# CoderDojo_Controller.net
KiCad netlist of a schematic drawn in EAGLE
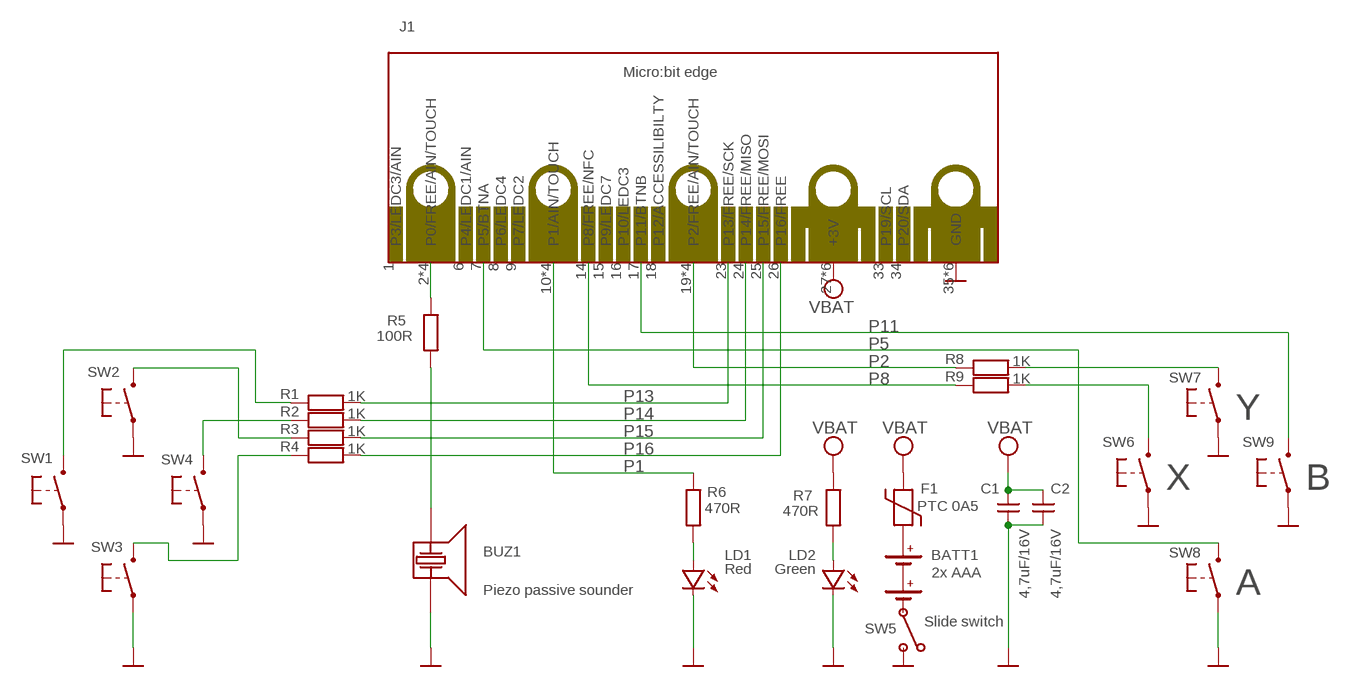
[diagram p0: schematic, sheet 1]

(export (version "E")
  (design (tool "Eeschema 10.0.6"))
  (components
    (comp (ref "BATT1")
      (value "CJ2XAAA")
      (footprint "eagle-import:SOCKET_2XAAA")
      (fields (field (name "VALUE_SHOWN") "2x AAA"))
      (libsource (lib "eagle-import") (part "CJ2XAAA"))
    )
    (comp (ref "BUZ1")
      (value "CBUZ9")
      (footprint "eagle-import:BUZZER9")
      (libsource (lib "eagle-import") (part "CBUZ9"))
    )
    (comp (ref "C1")
      (value "CC4U7A")
      (footprint "eagle-import:CAP_1206")
      (fields (field (name "VALUE_SHOWN") "4,7uF/16V"))
      (libsource (lib "eagle-import") (part "CC4U7A"))
    )
    (comp (ref "C2")
      (value "CC4U7A")
      (footprint "eagle-import:CAP_1206")
      (fields (field (name "VALUE_SHOWN") "4,7uF/16V"))
      (libsource (lib "eagle-import") (part "CC4U7A"))
    )
    (comp (ref "F1")
      (value "CFPOLY0A5B")
      (footprint "eagle-import:RES_1812")
      (fields (field (name "VALUE_SHOWN") "PTC 0A5"))
      (libsource (lib "eagle-import") (part "CFPOLY0A5B"))
    )
    (comp (ref "J1")
      (value "CJMBITH")
      (footprint "eagle-import:SOCKET_MBIT_H")
      (fields (field (name "VALUE_SHOWN") "Micro:bit edge"))
      (libsource (lib "eagle-import") (part "CJMBITH"))
    )
    (comp (ref "LD1")
      (value "CDLEDRDC")
      (footprint "eagle-import:LED_0805")
      (fields (field (name "VALUE_SHOWN") "Red"))
      (libsource (lib "eagle-import") (part "CDLEDRDC"))
    )
    (comp (ref "LD2")
      (value "CDLEDGNC")
      (footprint "eagle-import:LED_0805")
      (fields (field (name "VALUE_SHOWN") "Green"))
      (libsource (lib "eagle-import") (part "CDLEDGNC"))
    )
    (comp (ref "R1")
      (value "CR1KA")
      (footprint "eagle-import:RES_0805")
      (fields (field (name "VALUE_SHOWN") "1K"))
      (libsource (lib "eagle-import") (part "CR1KA"))
    )
    (comp (ref "R2")
      (value "CR1KA")
      (footprint "eagle-import:RES_0805")
      (fields (field (name "VALUE_SHOWN") "1K"))
      (libsource (lib "eagle-import") (part "CR1KA"))
    )
    (comp (ref "R3")
      (value "CR1KA")
      (footprint "eagle-import:RES_0805")
      (fields (field (name "VALUE_SHOWN") "1K"))
      (libsource (lib "eagle-import") (part "CR1KA"))
    )
    (comp (ref "R4")
      (value "CR1KA")
      (footprint "eagle-import:RES_0805")
      (fields (field (name "VALUE_SHOWN") "1K"))
      (libsource (lib "eagle-import") (part "CR1KA"))
    )
    (comp (ref "R5")
      (value "CR100RA")
      (footprint "eagle-import:RES_0805")
      (fields (field (name "VALUE_SHOWN") "100R"))
      (libsource (lib "eagle-import") (part "CR100RA"))
    )
    (comp (ref "R6")
      (value "CR470RA")
      (footprint "eagle-import:RES_0805")
      (fields (field (name "VALUE_SHOWN") "470R"))
      (libsource (lib "eagle-import") (part "CR470RA"))
    )
    (comp (ref "R7")
      (value "CR470RA")
      (footprint "eagle-import:RES_0805")
      (fields (field (name "VALUE_SHOWN") "470R"))
      (libsource (lib "eagle-import") (part "CR470RA"))
    )
    (comp (ref "R8")
      (value "CR1KA")
      (footprint "eagle-import:RES_0805")
      (fields (field (name "VALUE_SHOWN") "1K"))
      (libsource (lib "eagle-import") (part "CR1KA"))
    )
    (comp (ref "R9")
      (value "CR1KA")
      (footprint "eagle-import:RES_0805")
      (fields (field (name "VALUE_SHOWN") "1K"))
      (libsource (lib "eagle-import") (part "CR1KA"))
    )
    (comp (ref "SW1")
      (value "CSWPUSHA5")
      (footprint "eagle-import:SWITCH_PUSH_5MM")
      (libsource (lib "eagle-import") (part "CSWPUSHA5"))
    )
    (comp (ref "SW2")
      (value "CSWPUSHA5")
      (footprint "eagle-import:SWITCH_PUSH_5MM")
      (libsource (lib "eagle-import") (part "CSWPUSHA5"))
    )
    (comp (ref "SW3")
      (value "CSWPUSHA5")
      (footprint "eagle-import:SWITCH_PUSH_5MM")
      (libsource (lib "eagle-import") (part "CSWPUSHA5"))
    )
    (comp (ref "SW4")
      (value "CSWPUSHA5")
      (footprint "eagle-import:SWITCH_PUSH_5MM")
      (libsource (lib "eagle-import") (part "CSWPUSHA5"))
    )
    (comp (ref "SW5")
      (value "CSWSS12F23")
      (footprint "eagle-import:SWITCH_SS12F23")
      (fields (field (name "VALUE_SHOWN") "Slide switch"))
      (libsource (lib "eagle-import") (part "CSWSS12F23"))
    )
    (comp (ref "SW6")
      (value "CSWPUSHA5")
      (footprint "eagle-import:SWITCH_PUSH_5MM")
      (libsource (lib "eagle-import") (part "CSWPUSHA5"))
    )
    (comp (ref "SW7")
      (value "CSWPUSHA5")
      (footprint "eagle-import:SWITCH_PUSH_5MM")
      (libsource (lib "eagle-import") (part "CSWPUSHA5"))
    )
    (comp (ref "SW8")
      (value "CSWPUSHA5")
      (footprint "eagle-import:SWITCH_PUSH_5MM")
      (libsource (lib "eagle-import") (part "CSWPUSHA5"))
    )
    (comp (ref "SW9")
      (value "CSWPUSHA5")
      (footprint "eagle-import:SWITCH_PUSH_5MM")
      (libsource (lib "eagle-import") (part "CSWPUSHA5"))
    )
  )
  (nets
    (net (code "1") (name "/P1") (class "Default")
      (node (ref "J1") (pin "10") (pinfunction "P1/AIN/TOUCH_10") (pintype "bidirectional"))
      (node (ref "J1") (pin "11") (pinfunction "P1/AIN/TOUCH_11") (pintype "bidirectional"))
      (node (ref "J1") (pin "12") (pinfunction "P1/AIN/TOUCH_12") (pintype "bidirectional"))
      (node (ref "J1") (pin "13") (pinfunction "P1/AIN/TOUCH_13") (pintype "bidirectional"))
      (node (ref "R6") (pin "2") (pinfunction "2_2") (pintype "passive"))
    )
    (net (code "2") (name "/P2") (class "Default")
      (node (ref "J1") (pin "19") (pinfunction "P2/FREE/AIN/TOUCH_19") (pintype "bidirectional"))
      (node (ref "J1") (pin "20") (pinfunction "P2/FREE/AIN/TOUCH_20") (pintype "bidirectional"))
      (node (ref "J1") (pin "21") (pinfunction "P2/FREE/AIN/TOUCH_21") (pintype "bidirectional"))
      (node (ref "J1") (pin "22") (pinfunction "P2/FREE/AIN/TOUCH_22") (pintype "bidirectional"))
      (node (ref "R8") (pin "1") (pinfunction "1_1") (pintype "passive"))
    )
    (net (code "3") (name "/P5") (class "Default")
      (node (ref "J1") (pin "7") (pinfunction "P5/BTNA_7") (pintype "bidirectional"))
      (node (ref "SW8") (pin "1") (pinfunction "S_1") (pintype "passive"))
      (node (ref "SW8") (pin "2") (pinfunction "S_2") (pintype "passive"))
    )
    (net (code "4") (name "/P8") (class "Default")
      (node (ref "J1") (pin "14") (pinfunction "P8/FREE/NFC_14") (pintype "bidirectional"))
      (node (ref "R9") (pin "1") (pinfunction "1_1") (pintype "passive"))
    )
    (net (code "5") (name "/P11") (class "Default")
      (node (ref "J1") (pin "17") (pinfunction "P11/BTNB_17") (pintype "bidirectional"))
      (node (ref "SW9") (pin "1") (pinfunction "S_1") (pintype "passive"))
      (node (ref "SW9") (pin "2") (pinfunction "S_2") (pintype "passive"))
    )
    (net (code "6") (name "/P13") (class "Default")
      (node (ref "J1") (pin "23") (pinfunction "P13/FREE/SCK_23") (pintype "bidirectional"))
      (node (ref "R1") (pin "2") (pinfunction "2_2") (pintype "passive"))
    )
    (net (code "7") (name "/P14") (class "Default")
      (node (ref "J1") (pin "24") (pinfunction "P14/FREE/MISO_24") (pintype "bidirectional"))
      (node (ref "R2") (pin "2") (pinfunction "2_2") (pintype "passive"))
    )
    (net (code "8") (name "/P15") (class "Default")
      (node (ref "J1") (pin "25") (pinfunction "P15/FREE/MOSI_25") (pintype "bidirectional"))
      (node (ref "R3") (pin "2") (pinfunction "2_2") (pintype "passive"))
    )
    (net (code "9") (name "/P16") (class "Default")
      (node (ref "J1") (pin "26") (pinfunction "P16/FREE_26") (pintype "bidirectional"))
      (node (ref "R4") (pin "2") (pinfunction "2_2") (pintype "passive"))
    )
    (net (code "10") (name "GND") (class "Default")
      (node (ref "BUZ1") (pin "2") (pinfunction "P$2_2") (pintype "bidirectional"))
      (node (ref "C1") (pin "1") (pinfunction "1_1") (pintype "passive"))
      (node (ref "C2") (pin "1") (pinfunction "1_1") (pintype "passive"))
      (node (ref "J1") (pin "35") (pinfunction "GND_35") (pintype "bidirectional"))
      (node (ref "J1") (pin "36") (pinfunction "GND_36") (pintype "bidirectional"))
      (node (ref "J1") (pin "37") (pinfunction "GND_37") (pintype "bidirectional"))
      (node (ref "J1") (pin "38") (pinfunction "GND_38") (pintype "bidirectional"))
      (node (ref "J1") (pin "39") (pinfunction "GND_39") (pintype "bidirectional"))
      (node (ref "J1") (pin "40") (pinfunction "GND_40") (pintype "bidirectional"))
      (node (ref "LD1") (pin "C") (pinfunction "C_C") (pintype "passive"))
      (node (ref "LD2") (pin "C") (pinfunction "C_C") (pintype "passive"))
      (node (ref "SW1") (pin "3") (pinfunction "P_3") (pintype "passive"))
      (node (ref "SW1") (pin "4") (pinfunction "P_4") (pintype "passive"))
      (node (ref "SW2") (pin "3") (pinfunction "P_3") (pintype "passive"))
      (node (ref "SW2") (pin "4") (pinfunction "P_4") (pintype "passive"))
      (node (ref "SW3") (pin "3") (pinfunction "P_3") (pintype "passive"))
      (node (ref "SW3") (pin "4") (pinfunction "P_4") (pintype "passive"))
      (node (ref "SW4") (pin "3") (pinfunction "P_3") (pintype "passive"))
      (node (ref "SW4") (pin "4") (pinfunction "P_4") (pintype "passive"))
      (node (ref "SW5") (pin "3") (pinfunction "B_3") (pintype "bidirectional"))
      (node (ref "SW6") (pin "3") (pinfunction "P_3") (pintype "passive"))
      (node (ref "SW6") (pin "4") (pinfunction "P_4") (pintype "passive"))
      (node (ref "SW7") (pin "3") (pinfunction "P_3") (pintype "passive"))
      (node (ref "SW7") (pin "4") (pinfunction "P_4") (pintype "passive"))
      (node (ref "SW8") (pin "3") (pinfunction "P_3") (pintype "passive"))
      (node (ref "SW8") (pin "4") (pinfunction "P_4") (pintype "passive"))
      (node (ref "SW9") (pin "3") (pinfunction "P_3") (pintype "passive"))
      (node (ref "SW9") (pin "4") (pinfunction "P_4") (pintype "passive"))
    )
    (net (code "11") (name "Net-(BATT1-+)") (class "Default")
      (node (ref "BATT1") (pin "POS") (pinfunction "+_POS") (pintype "passive"))
      (node (ref "F1") (pin "1") (pinfunction "1_1") (pintype "bidirectional"))
    )
    (net (code "12") (name "Net-(BATT1--)") (class "Default")
      (node (ref "BATT1") (pin "NEG") (pinfunction "-_NEG") (pintype "passive"))
      (node (ref "SW5") (pin "2") (pinfunction "CEN_2") (pintype "bidirectional"))
    )
    (net (code "13") (name "Net-(BUZ1-P$1)") (class "Default")
      (node (ref "BUZ1") (pin "1") (pinfunction "P$1_1") (pintype "bidirectional"))
      (node (ref "R5") (pin "1") (pinfunction "1_1") (pintype "passive"))
    )
    (net (code "14") (name "Net-(J1-P0{slash}FREE{slash}AIN{slash}TOUCH-Pad2)") (class "Default")
      (node (ref "J1") (pin "2") (pinfunction "P0/FREE/AIN/TOUCH_2") (pintype "bidirectional"))
      (node (ref "J1") (pin "3") (pinfunction "P0/FREE/AIN/TOUCH_3") (pintype "bidirectional"))
      (node (ref "J1") (pin "4") (pinfunction "P0/FREE/AIN/TOUCH_4") (pintype "bidirectional"))
      (node (ref "J1") (pin "5") (pinfunction "P0/FREE/AIN/TOUCH_5") (pintype "bidirectional"))
      (node (ref "R5") (pin "2") (pinfunction "2_2") (pintype "passive"))
    )
    (net (code "15") (name "Net-(LD1-PadA)") (class "Default")
      (node (ref "LD1") (pin "A") (pinfunction "A_A") (pintype "passive"))
      (node (ref "R6") (pin "1") (pinfunction "1_1") (pintype "passive"))
    )
    (net (code "16") (name "Net-(LD2-PadA)") (class "Default")
      (node (ref "LD2") (pin "A") (pinfunction "A_A") (pintype "passive"))
      (node (ref "R7") (pin "1") (pinfunction "1_1") (pintype "passive"))
    )
    (net (code "17") (name "Net-(R1-Pad1)") (class "Default")
      (node (ref "R1") (pin "1") (pinfunction "1_1") (pintype "passive"))
      (node (ref "SW1") (pin "1") (pinfunction "S_1") (pintype "passive"))
      (node (ref "SW1") (pin "2") (pinfunction "S_2") (pintype "passive"))
    )
    (net (code "18") (name "Net-(R2-Pad1)") (class "Default")
      (node (ref "R2") (pin "1") (pinfunction "1_1") (pintype "passive"))
      (node (ref "SW4") (pin "1") (pinfunction "S_1") (pintype "passive"))
      (node (ref "SW4") (pin "2") (pinfunction "S_2") (pintype "passive"))
    )
    (net (code "19") (name "Net-(R3-Pad1)") (class "Default")
      (node (ref "R3") (pin "1") (pinfunction "1_1") (pintype "passive"))
      (node (ref "SW2") (pin "1") (pinfunction "S_1") (pintype "passive"))
      (node (ref "SW2") (pin "2") (pinfunction "S_2") (pintype "passive"))
    )
    (net (code "20") (name "Net-(R4-Pad1)") (class "Default")
      (node (ref "R4") (pin "1") (pinfunction "1_1") (pintype "passive"))
      (node (ref "SW3") (pin "1") (pinfunction "S_1") (pintype "passive"))
      (node (ref "SW3") (pin "2") (pinfunction "S_2") (pintype "passive"))
    )
    (net (code "21") (name "Net-(R8-Pad2)") (class "Default")
      (node (ref "R8") (pin "2") (pinfunction "2_2") (pintype "passive"))
      (node (ref "SW7") (pin "1") (pinfunction "S_1") (pintype "passive"))
      (node (ref "SW7") (pin "2") (pinfunction "S_2") (pintype "passive"))
    )
    (net (code "22") (name "Net-(R9-Pad2)") (class "Default")
      (node (ref "R9") (pin "2") (pinfunction "2_2") (pintype "passive"))
      (node (ref "SW6") (pin "1") (pinfunction "S_1") (pintype "passive"))
      (node (ref "SW6") (pin "2") (pinfunction "S_2") (pintype "passive"))
    )
    (net (code "23") (name "SUPPLY_VBAT") (class "Default")
      (node (ref "C1") (pin "2") (pinfunction "2_2") (pintype "passive"))
      (node (ref "C2") (pin "2") (pinfunction "2_2") (pintype "passive"))
      (node (ref "F1") (pin "2") (pinfunction "2_2") (pintype "bidirectional"))
      (node (ref "J1") (pin "27") (pinfunction "+3V_27") (pintype "bidirectional"))
      (node (ref "J1") (pin "28") (pinfunction "+3V_28") (pintype "bidirectional"))
      (node (ref "J1") (pin "29") (pinfunction "+3V_29") (pintype "bidirectional"))
      (node (ref "J1") (pin "30") (pinfunction "+3V_30") (pintype "bidirectional"))
      (node (ref "J1") (pin "31") (pinfunction "+3V_31") (pintype "bidirectional"))
      (node (ref "J1") (pin "32") (pinfunction "+3V_32") (pintype "bidirectional"))
      (node (ref "R7") (pin "2") (pinfunction "2_2") (pintype "passive"))
    )
    (net (code "24") (name "unconnected-(J1-P3{slash}LEDC3{slash}AIN-Pad1)") (class "Default")
      (node (ref "J1") (pin "1") (pinfunction "P3/LEDC3/AIN_1") (pintype "bidirectional"))
    )
    (net (code "25") (name "unconnected-(J1-P4{slash}LEDC1{slash}AIN-Pad6)") (class "Default")
      (node (ref "J1") (pin "6") (pinfunction "P4/LEDC1/AIN_6") (pintype "bidirectional"))
    )
    (net (code "26") (name "unconnected-(J1-P6{slash}LEDC4-Pad8)") (class "Default")
      (node (ref "J1") (pin "8") (pinfunction "P6/LEDC4_8") (pintype "bidirectional"))
    )
    (net (code "27") (name "unconnected-(J1-P7{slash}LEDC2-Pad9)") (class "Default")
      (node (ref "J1") (pin "9") (pinfunction "P7/LEDC2_9") (pintype "bidirectional"))
    )
    (net (code "28") (name "unconnected-(J1-P9{slash}LEDC7-Pad15)") (class "Default")
      (node (ref "J1") (pin "15") (pinfunction "P9/LEDC7_15") (pintype "bidirectional"))
    )
    (net (code "29") (name "unconnected-(J1-P10{slash}LEDC3-Pad16)") (class "Default")
      (node (ref "J1") (pin "16") (pinfunction "P10/LEDC3_16") (pintype "bidirectional"))
    )
    (net (code "30") (name "unconnected-(J1-P12{slash}ACCESSILIBILTY-Pad18)") (class "Default")
      (node (ref "J1") (pin "18") (pinfunction "P12/ACCESSILIBILTY_18") (pintype "bidirectional"))
    )
    (net (code "31") (name "unconnected-(J1-P19{slash}SCL-Pad33)") (class "Default")
      (node (ref "J1") (pin "33") (pinfunction "P19/SCL_33") (pintype "bidirectional"))
    )
    (net (code "32") (name "unconnected-(J1-P20{slash}SDA-Pad34)") (class "Default")
      (node (ref "J1") (pin "34") (pinfunction "P20/SDA_34") (pintype "bidirectional"))
    )
    (net (code "33") (name "unconnected-(SW5-A-Pad1)") (class "Default")
      (node (ref "SW5") (pin "1") (pinfunction "A_1") (pintype "bidirectional"))
    )
  )
)
